# Microcontroller.net
KiCad netlist of a schematic drawn in Altium Designer
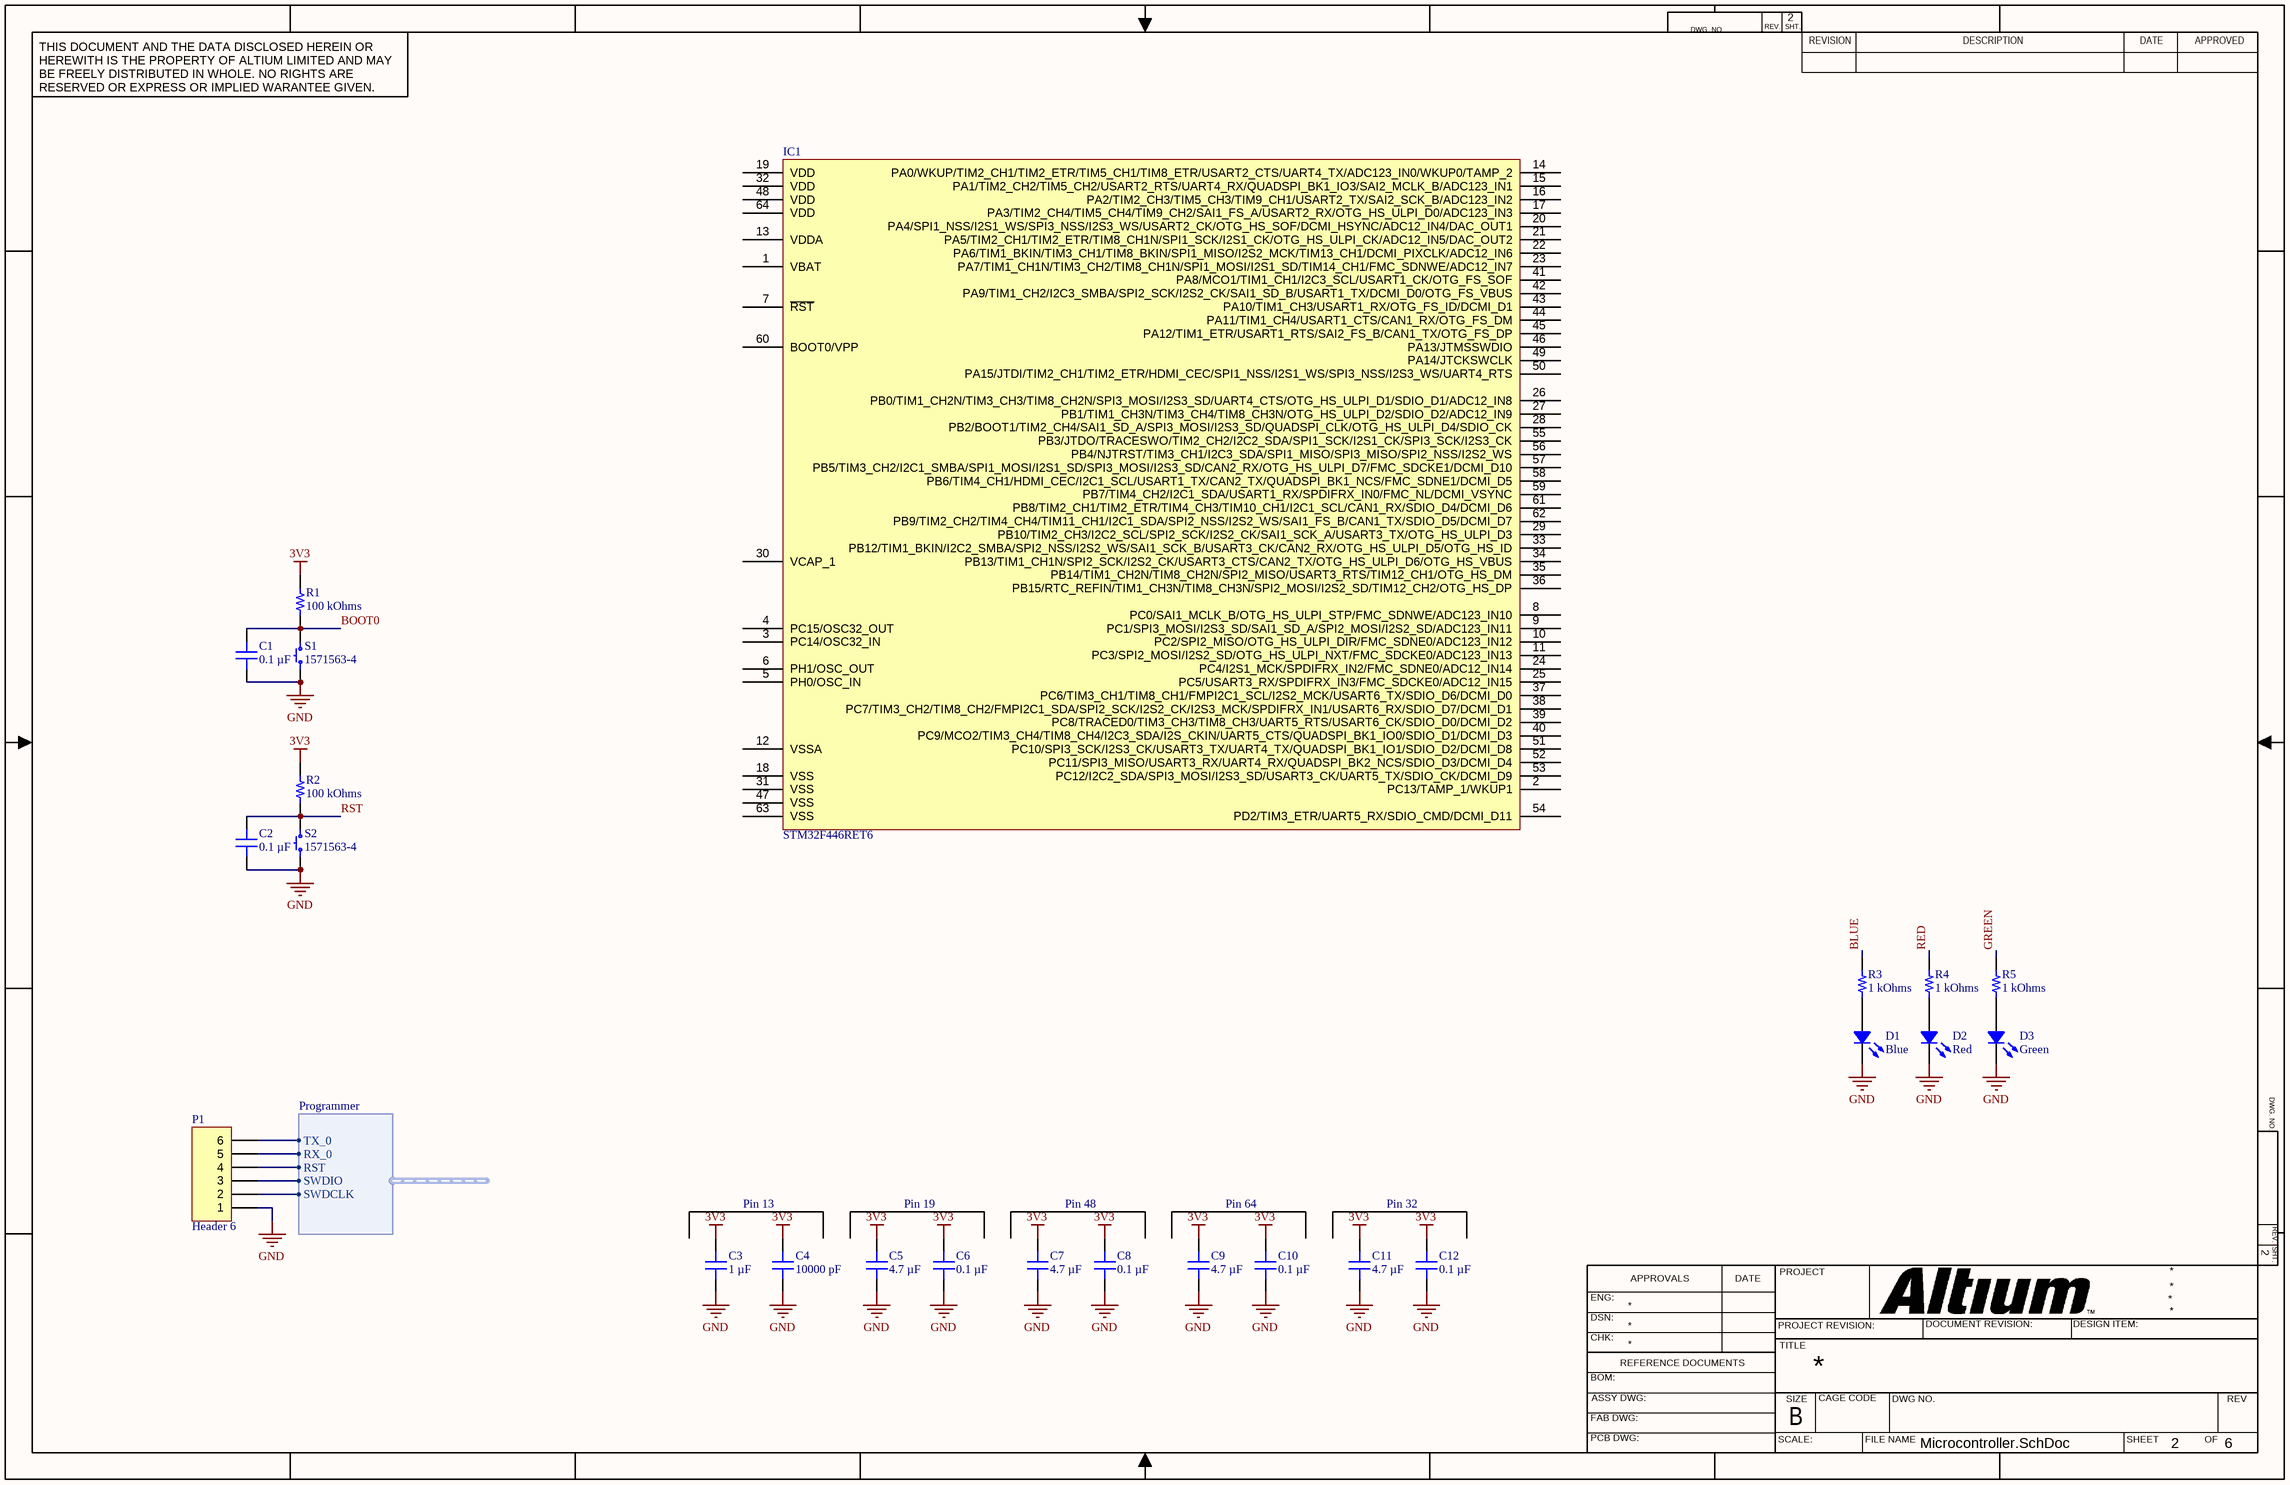
[diagram p0: Microcontroller.SchDoc]

(export (version "E")
  (design (tool "Eeschema 10.0.6"))
  (components
    (comp (ref "C1")
      (value "0.1 µF")
      (footprint "CAP 0603_1608")
      (description "CAP CER 0.1UF 50V X7R 0603")
      (fields (field (name "PART NUMBER") "C0603C104K5RAC7411") (field (name "MANUFACTURER") "KEMET"))
      (libsource (lib "Celestial Altium Library - altium_library") (part "Capacitor"))
    )
    (comp (ref "C2")
      (value "0.1 µF")
      (footprint "CAP 0603_1608")
      (description "CAP CER 0.1UF 50V X7R 0603")
      (fields (field (name "PART NUMBER") "C0603C104K5RAC7411") (field (name "MANUFACTURER") "KEMET"))
      (libsource (lib "Celestial Altium Library - altium_library") (part "Capacitor"))
    )
    (comp (ref "C3")
      (value "1 µF")
      (footprint "CAP 0603_1608")
      (description "CAP CER 1UF 10V X7R 0603")
      (fields (field (name "PART NUMBER") "CC0603KRX7R6BB105") (field (name "MANUFACTURER") "Yageo"))
      (libsource (lib "Celestial Altium Library - altium_library") (part "Capacitor"))
    )
    (comp (ref "C4")
      (value "10000 pF")
      (footprint "CAP 0603_1608")
      (description "CAP CER 0603 10NF 16V X7R 10%")
      (fields (field (name "PART NUMBER") "C0603C103K4RECAUTO") (field (name "MANUFACTURER") "KEMET"))
      (libsource (lib "Celestial Altium Library - altium_library") (part "Capacitor"))
    )
    (comp (ref "C5")
      (value "4.7 µF")
      (footprint "CAP 0603_1608")
      (description "CAP CER 4.7UF 10V X5R 0603")
      (fields
        (field (name "PART NUMBER") "CL10A475KP8NNNC")
        (field (name "MANUFACTURER") "Samsung Electro-Mechanics")
      )
      (libsource (lib "Celestial Altium Library - altium_library") (part "Capacitor"))
    )
    (comp (ref "C6")
      (value "0.1 µF")
      (footprint "CAP 0603_1608")
      (description "CAP CER 0.1UF 50V X7R 0603")
      (fields (field (name "PART NUMBER") "C0603C104K5RAC7411") (field (name "MANUFACTURER") "KEMET"))
      (libsource (lib "Celestial Altium Library - altium_library") (part "Capacitor"))
    )
    (comp (ref "C7")
      (value "4.7 µF")
      (footprint "CAP 0603_1608")
      (description "CAP CER 4.7UF 10V X5R 0603")
      (fields
        (field (name "PART NUMBER") "CL10A475KP8NNNC")
        (field (name "MANUFACTURER") "Samsung Electro-Mechanics")
      )
      (libsource (lib "Celestial Altium Library - altium_library") (part "Capacitor"))
    )
    (comp (ref "C8")
      (value "0.1 µF")
      (footprint "CAP 0603_1608")
      (description "CAP CER 0.1UF 50V X7R 0603")
      (fields (field (name "PART NUMBER") "C0603C104K5RAC7411") (field (name "MANUFACTURER") "KEMET"))
      (libsource (lib "Celestial Altium Library - altium_library") (part "Capacitor"))
    )
    (comp (ref "C9")
      (value "4.7 µF")
      (footprint "CAP 0603_1608")
      (description "CAP CER 4.7UF 10V X5R 0603")
      (fields
        (field (name "PART NUMBER") "CL10A475KP8NNNC")
        (field (name "MANUFACTURER") "Samsung Electro-Mechanics")
      )
      (libsource (lib "Celestial Altium Library - altium_library") (part "Capacitor"))
    )
    (comp (ref "C10")
      (value "0.1 µF")
      (footprint "CAP 0603_1608")
      (description "CAP CER 0.1UF 50V X7R 0603")
      (fields (field (name "PART NUMBER") "C0603C104K5RAC7411") (field (name "MANUFACTURER") "KEMET"))
      (libsource (lib "Celestial Altium Library - altium_library") (part "Capacitor"))
    )
    (comp (ref "C11")
      (value "4.7 µF")
      (footprint "CAP 0603_1608")
      (description "CAP CER 4.7UF 10V X5R 0603")
      (fields
        (field (name "PART NUMBER") "CL10A475KP8NNNC")
        (field (name "MANUFACTURER") "Samsung Electro-Mechanics")
      )
      (libsource (lib "Celestial Altium Library - altium_library") (part "Capacitor"))
    )
    (comp (ref "C12")
      (value "0.1 µF")
      (footprint "CAP 0603_1608")
      (description "CAP CER 0.1UF 50V X7R 0603")
      (fields (field (name "PART NUMBER") "C0603C104K5RAC7411") (field (name "MANUFACTURER") "KEMET"))
      (libsource (lib "Celestial Altium Library - altium_library") (part "Capacitor"))
    )
    (comp (ref "D1")
      (value "Blue")
      (footprint "LED 0603_1608 BLUE")
      (description "LED BLUE CLEAR CHIP SMD")
      (fields (field (name "PART NUMBER") "LTST-C193TBKT-5A") (field (name "MANUFACTURER") "Lite-On Inc."))
      (libsource (lib "Celestial Altium Library - altium_library") (part "LED"))
    )
    (comp (ref "D2")
      (value "Red")
      (footprint "LED 0603_1608 RED")
      (description "LED RED CLEAR CHIP SMD")
      (fields (field (name "PART NUMBER") "LTST-C190KAKT") (field (name "MANUFACTURER") "Lite-On Inc."))
      (libsource (lib "Celestial Altium Library - altium_library") (part "LED"))
    )
    (comp (ref "D3")
      (value "Green")
      (footprint "LED 0603_1608 GREEN")
      (description "LED GREEN CLEAR 2SMD")
      (fields (field (name "PART NUMBER") "XZVGT53W-6") (field (name "MANUFACTURER") "SunLED"))
      (libsource (lib "Celestial Altium Library - altium_library") (part "LED"))
    )
    (comp (ref "IC1")
      (value "STM32F446RET6")
      (footprint "ST LQFP-64 10X10MM")
      (description "IC MCU 32BIT 512KB FLASH 64LQFP")
      (fields (field (name "MANUFACTURER") "STMicroelectronics"))
      (libsource (lib "Celestial Altium Library - altium_library") (part "ST STM32F446 64PIN"))
    )
    (comp (ref "P1")
      (value "Header 6")
      (footprint "HDR1X6")
      (description "Header, 6-Pin")
      (fields (field (name "PUBLISHER") "Altium Limited"))
      (libsource (lib "Miscellaneous Connectors") (part "Header 6"))
    )
    (comp (ref "R1")
      (value "100 kOhms")
      (footprint "RES 0603_1608")
      (description "RES 100K OHM 1% 1/10W 0603")
      (fields (field (name "PART NUMBER") "CRCW0603100KFKEAC") (field (name "MANUFACTURER") "Vishay Dale"))
      (libsource (lib "Celestial Altium Library - altium_library") (part "Resistor"))
    )
    (comp (ref "R2")
      (value "100 kOhms")
      (footprint "RES 0603_1608")
      (description "RES 100K OHM 1% 1/10W 0603")
      (fields (field (name "PART NUMBER") "CRCW0603100KFKEAC") (field (name "MANUFACTURER") "Vishay Dale"))
      (libsource (lib "Celestial Altium Library - altium_library") (part "Resistor"))
    )
    (comp (ref "R3")
      (value "1 kOhms")
      (footprint "RES 0603_1608")
      (description "RES SMD 1K OHM 1% 1/10W 0603")
      (fields (field (name "PART NUMBER") "RT0603FRE071KL") (field (name "MANUFACTURER") "Yageo"))
      (libsource (lib "Celestial Altium Library - altium_library") (part "Resistor"))
    )
    (comp (ref "R4")
      (value "1 kOhms")
      (footprint "RES 0603_1608")
      (description "RES SMD 1K OHM 1% 1/10W 0603")
      (fields (field (name "PART NUMBER") "RT0603FRE071KL") (field (name "MANUFACTURER") "Yageo"))
      (libsource (lib "Celestial Altium Library - altium_library") (part "Resistor"))
    )
    (comp (ref "R5")
      (value "1 kOhms")
      (footprint "RES 0603_1608")
      (description "RES SMD 1K OHM 1% 1/10W 0603")
      (fields (field (name "PART NUMBER") "RT0603FRE071KL") (field (name "MANUFACTURER") "Yageo"))
      (libsource (lib "Celestial Altium Library - altium_library") (part "Resistor"))
    )
    (comp (ref "S1")
      (value "1571563-4")
      (footprint "TE FSM4JSMA")
      (description "SWITCH TACTILE SPST-NO 0.05A 24V")
      (fields (field (name "MANUFACTURER") "TE Connectivity ALCOSWITCH Switches"))
      (libsource (lib "Celestial Altium Library - altium_library") (part "SPST-NO 4 PIN"))
    )
    (comp (ref "S2")
      (value "1571563-4")
      (footprint "TE FSM4JSMA")
      (description "SWITCH TACTILE SPST-NO 0.05A 24V")
      (fields (field (name "MANUFACTURER") "TE Connectivity ALCOSWITCH Switches"))
      (libsource (lib "Celestial Altium Library - altium_library") (part "SPST-NO 4 PIN"))
    )
  )
  (nets
    (net (code "2") (name "/BLUE") (class "Default")
      (node (ref "R3") (pin "2") (pinfunction "2_2") (pintype "passive"))
    )
    (net (code "3") (name "/BOOT0") (class "Default")
      (node (ref "C1") (pin "2") (pinfunction "2_2") (pintype "passive"))
      (node (ref "R1") (pin "1") (pinfunction "1_1") (pintype "passive"))
      (node (ref "S1") (pin "3") (pinfunction "3_3") (pintype "passive"))
      (node (ref "S1") (pin "4") (pinfunction "4_4") (pintype "passive"))
    )
    (net (code "4") (name "/GREEN") (class "Default")
      (node (ref "R5") (pin "2") (pinfunction "2_2") (pintype "passive"))
    )
    (net (code "5") (name "/RED") (class "Default")
      (node (ref "R4") (pin "2") (pinfunction "2_2") (pintype "passive"))
    )
    (net (code "6") (name "/RST") (class "Default")
      (node (ref "C2") (pin "2") (pinfunction "2_2") (pintype "passive"))
      (node (ref "R2") (pin "1") (pinfunction "1_1") (pintype "passive"))
      (node (ref "S2") (pin "3") (pinfunction "3_3") (pintype "passive"))
      (node (ref "S2") (pin "4") (pinfunction "4_4") (pintype "passive"))
    )
    (net (code "7") (name "/RX_0") (class "Default")
      (node (ref "P1") (pin "5") (pinfunction "5_5") (pintype "passive"))
    )
    (net (code "8") (name "/SWDCLK") (class "Default")
      (node (ref "P1") (pin "2") (pinfunction "2_2") (pintype "passive"))
    )
    (net (code "9") (name "/SWDIO") (class "Default")
      (node (ref "P1") (pin "3") (pinfunction "3_3") (pintype "passive"))
    )
    (net (code "10") (name "/TX_0") (class "Default")
      (node (ref "P1") (pin "6") (pinfunction "6_6") (pintype "passive"))
    )
    (net (code "12") (name "3V3") (class "Default")
      (node (ref "C10") (pin "2") (pinfunction "2_2") (pintype "passive"))
      (node (ref "C11") (pin "2") (pinfunction "2_2") (pintype "passive"))
      (node (ref "C12") (pin "2") (pinfunction "2_2") (pintype "passive"))
      (node (ref "C3") (pin "2") (pinfunction "2_2") (pintype "passive"))
      (node (ref "C4") (pin "2") (pinfunction "2_2") (pintype "passive"))
      (node (ref "C5") (pin "2") (pinfunction "2_2") (pintype "passive"))
      (node (ref "C6") (pin "2") (pinfunction "2_2") (pintype "passive"))
      (node (ref "C7") (pin "2") (pinfunction "2_2") (pintype "passive"))
      (node (ref "C8") (pin "2") (pinfunction "2_2") (pintype "passive"))
      (node (ref "C9") (pin "2") (pinfunction "2_2") (pintype "passive"))
      (node (ref "R1") (pin "2") (pinfunction "2_2") (pintype "passive"))
      (node (ref "R2") (pin "2") (pinfunction "2_2") (pintype "passive"))
    )
    (net (code "13") (name "GND") (class "Default")
      (node (ref "C1") (pin "1") (pinfunction "1_1") (pintype "passive"))
      (node (ref "C10") (pin "1") (pinfunction "1_1") (pintype "passive"))
      (node (ref "C11") (pin "1") (pinfunction "1_1") (pintype "passive"))
      (node (ref "C12") (pin "1") (pinfunction "1_1") (pintype "passive"))
      (node (ref "C2") (pin "1") (pinfunction "1_1") (pintype "passive"))
      (node (ref "C3") (pin "1") (pinfunction "1_1") (pintype "passive"))
      (node (ref "C4") (pin "1") (pinfunction "1_1") (pintype "passive"))
      (node (ref "C5") (pin "1") (pinfunction "1_1") (pintype "passive"))
      (node (ref "C6") (pin "1") (pinfunction "1_1") (pintype "passive"))
      (node (ref "C7") (pin "1") (pinfunction "1_1") (pintype "passive"))
      (node (ref "C8") (pin "1") (pinfunction "1_1") (pintype "passive"))
      (node (ref "C9") (pin "1") (pinfunction "1_1") (pintype "passive"))
      (node (ref "D1") (pin "2") (pinfunction "2_2") (pintype "passive"))
      (node (ref "D2") (pin "2") (pinfunction "2_2") (pintype "passive"))
      (node (ref "D3") (pin "2") (pinfunction "2_2") (pintype "passive"))
      (node (ref "P1") (pin "1") (pinfunction "1_1") (pintype "passive"))
      (node (ref "S1") (pin "1") (pinfunction "1_1") (pintype "passive"))
      (node (ref "S1") (pin "2") (pinfunction "2_2") (pintype "passive"))
      (node (ref "S2") (pin "1") (pinfunction "1_1") (pintype "passive"))
      (node (ref "S2") (pin "2") (pinfunction "2_2") (pintype "passive"))
    )
    (net (code "14") (name "Net-(D1-Pad1)") (class "Default")
      (node (ref "D1") (pin "1") (pinfunction "1_1") (pintype "passive"))
      (node (ref "R3") (pin "1") (pinfunction "1_1") (pintype "passive"))
    )
    (net (code "15") (name "Net-(D2-Pad1)") (class "Default")
      (node (ref "D2") (pin "1") (pinfunction "1_1") (pintype "passive"))
      (node (ref "R4") (pin "1") (pinfunction "1_1") (pintype "passive"))
    )
    (net (code "16") (name "Net-(D3-Pad1)") (class "Default")
      (node (ref "D3") (pin "1") (pinfunction "1_1") (pintype "passive"))
      (node (ref "R5") (pin "1") (pinfunction "1_1") (pintype "passive"))
    )
    (net (code "17") (name "unconnected-(IC1-BOOT0{slash}VPP-Pad60)") (class "Default")
      (node (ref "IC1") (pin "60") (pinfunction "BOOT0/VPP_60") (pintype "passive"))
    )
    (net (code "18") (name "unconnected-(IC1-PA0{slash}WKUP{slash}TIM2_CH1{slash}TIM2_ETR{slash}TIM5_CH1{slash}TIM8_ETR{slash}USART2_CTS{slash}UART4_TX{slash}ADC123_IN0{slash}WKUP0{slash}TAMP_2-Pad14)") (class "Default")
      (node (ref "IC1") (pin "14") (pinfunction "PA0/WKUP/TIM2_CH1/TIM2_ETR/TIM5_CH1/TIM8_ETR/USART2_CTS/UART4_TX/ADC123_IN0/WKUP0/TAMP_2_14") (pintype "passive"))
    )
    (net (code "19") (name "unconnected-(IC1-PA1{slash}TIM2_CH2{slash}TIM5_CH2{slash}USART2_RTS{slash}UART4_RX{slash}QUADSPI_BK1_IO3{slash}SAI2_MCLK_B{slash}ADC123_IN1-Pad15)") (class "Default")
      (node (ref "IC1") (pin "15") (pinfunction "PA1/TIM2_CH2/TIM5_CH2/USART2_RTS/UART4_RX/QUADSPI_BK1_IO3/SAI2_MCLK_B/ADC123_IN1_15") (pintype "passive"))
    )
    (net (code "20") (name "unconnected-(IC1-PA2{slash}TIM2_CH3{slash}TIM5_CH3{slash}TIM9_CH1{slash}USART2_TX{slash}SAI2_SCK_B{slash}ADC123_IN2-Pad16)") (class "Default")
      (node (ref "IC1") (pin "16") (pinfunction "PA2/TIM2_CH3/TIM5_CH3/TIM9_CH1/USART2_TX/SAI2_SCK_B/ADC123_IN2_16") (pintype "passive"))
    )
    (net (code "21") (name "unconnected-(IC1-PA3{slash}TIM2_CH4{slash}TIM5_CH4{slash}TIM9_CH2{slash}SAI1_FS_A{slash}USART2_RX{slash}OTG_HS_ULPI_D0{slash}ADC123_IN3-Pad17)") (class "Default")
      (node (ref "IC1") (pin "17") (pinfunction "PA3/TIM2_CH4/TIM5_CH4/TIM9_CH2/SAI1_FS_A/USART2_RX/OTG_HS_ULPI_D0/ADC123_IN3_17") (pintype "passive"))
    )
    (net (code "22") (name "unconnected-(IC1-PA4{slash}SPI1_NSS{slash}I2S1_WS{slash}SPI3_NSS{slash}I2S3_WS{slash}USART2_CK{slash}OTG_HS_SOF{slash}DCMI_HSYNC{slash}ADC12_IN4{slash}DAC_OUT1-Pad20)") (class "Default")
      (node (ref "IC1") (pin "20") (pinfunction "PA4/SPI1_NSS/I2S1_WS/SPI3_NSS/I2S3_WS/USART2_CK/OTG_HS_SOF/DCMI_HSYNC/ADC12_IN4/DAC_OUT1_20") (pintype "passive"))
    )
    (net (code "23") (name "unconnected-(IC1-PA5{slash}TIM2_CH1{slash}TIM2_ETR{slash}TIM8_CH1N{slash}SPI1_SCK{slash}I2S1_CK{slash}OTG_HS_ULPI_CK{slash}ADC12_IN5{slash}DAC_OUT2-Pad21)") (class "Default")
      (node (ref "IC1") (pin "21") (pinfunction "PA5/TIM2_CH1/TIM2_ETR/TIM8_CH1N/SPI1_SCK/I2S1_CK/OTG_HS_ULPI_CK/ADC12_IN5/DAC_OUT2_21") (pintype "passive"))
    )
    (net (code "24") (name "unconnected-(IC1-PA6{slash}TIM1_BKIN{slash}TIM3_CH1{slash}TIM8_BKIN{slash}SPI1_MISO{slash}I2S2_MCK{slash}TIM13_CH1{slash}DCMI_PIXCLK{slash}ADC12_IN6-Pad22)") (class "Default")
      (node (ref "IC1") (pin "22") (pinfunction "PA6/TIM1_BKIN/TIM3_CH1/TIM8_BKIN/SPI1_MISO/I2S2_MCK/TIM13_CH1/DCMI_PIXCLK/ADC12_IN6_22") (pintype "passive"))
    )
    (net (code "25") (name "unconnected-(IC1-PA7{slash}TIM1_CH1N{slash}TIM3_CH2{slash}TIM8_CH1N{slash}SPI1_MOSI{slash}I2S1_SD{slash}TIM14_CH1{slash}FMC_SDNWE{slash}ADC12_IN7-Pad23)") (class "Default")
      (node (ref "IC1") (pin "23") (pinfunction "PA7/TIM1_CH1N/TIM3_CH2/TIM8_CH1N/SPI1_MOSI/I2S1_SD/TIM14_CH1/FMC_SDNWE/ADC12_IN7_23") (pintype "passive"))
    )
    (net (code "26") (name "unconnected-(IC1-PA8{slash}MCO1{slash}TIM1_CH1{slash}I2C3_SCL{slash}USART1_CK{slash}OTG_FS_SOF-Pad41)") (class "Default")
      (node (ref "IC1") (pin "41") (pinfunction "PA8/MCO1/TIM1_CH1/I2C3_SCL/USART1_CK/OTG_FS_SOF_41") (pintype "passive"))
    )
    (net (code "27") (name "unconnected-(IC1-PA9{slash}TIM1_CH2{slash}I2C3_SMBA{slash}SPI2_SCK{slash}I2S2_CK{slash}SAI1_SD_B{slash}USART1_TX{slash}DCMI_D0{slash}OTG_FS_VBUS-Pad42)") (class "Default")
      (node (ref "IC1") (pin "42") (pinfunction "PA9/TIM1_CH2/I2C3_SMBA/SPI2_SCK/I2S2_CK/SAI1_SD_B/USART1_TX/DCMI_D0/OTG_FS_VBUS_42") (pintype "passive"))
    )
    (net (code "28") (name "unconnected-(IC1-PA10{slash}TIM1_CH3{slash}USART1_RX{slash}OTG_FS_ID{slash}DCMI_D1-Pad43)") (class "Default")
      (node (ref "IC1") (pin "43") (pinfunction "PA10/TIM1_CH3/USART1_RX/OTG_FS_ID/DCMI_D1_43") (pintype "passive"))
    )
    (net (code "29") (name "unconnected-(IC1-PA11{slash}TIM1_CH4{slash}USART1_CTS{slash}CAN1_RX{slash}OTG_FS_DM-Pad44)") (class "Default")
      (node (ref "IC1") (pin "44") (pinfunction "PA11/TIM1_CH4/USART1_CTS/CAN1_RX/OTG_FS_DM_44") (pintype "passive"))
    )
    (net (code "30") (name "unconnected-(IC1-PA12{slash}TIM1_ETR{slash}USART1_RTS{slash}SAI2_FS_B{slash}CAN1_TX{slash}OTG_FS_DP-Pad45)") (class "Default")
      (node (ref "IC1") (pin "45") (pinfunction "PA12/TIM1_ETR/USART1_RTS/SAI2_FS_B/CAN1_TX/OTG_FS_DP_45") (pintype "passive"))
    )
    (net (code "31") (name "unconnected-(IC1-PA13{slash}JTMSSWDIO-Pad46)") (class "Default")
      (node (ref "IC1") (pin "46") (pinfunction "PA13/JTMSSWDIO_46") (pintype "passive"))
    )
    (net (code "32") (name "unconnected-(IC1-PA14{slash}JTCKSWCLK-Pad49)") (class "Default")
      (node (ref "IC1") (pin "49") (pinfunction "PA14/JTCKSWCLK_49") (pintype "passive"))
    )
    (net (code "33") (name "unconnected-(IC1-PA15{slash}JTDI{slash}TIM2_CH1{slash}TIM2_ETR{slash}HDMI_CEC{slash}SPI1_NSS{slash}I2S1_WS{slash}SPI3_NSS{slash}I2S3_WS{slash}UART4_RTS-Pad50)") (class "Default")
      (node (ref "IC1") (pin "50") (pinfunction "PA15/JTDI/TIM2_CH1/TIM2_ETR/HDMI_CEC/SPI1_NSS/I2S1_WS/SPI3_NSS/I2S3_WS/UART4_RTS_50") (pintype "passive"))
    )
    (net (code "34") (name "unconnected-(IC1-PB0{slash}TIM1_CH2N{slash}TIM3_CH3{slash}TIM8_CH2N{slash}SPI3_MOSI{slash}I2S3_SD{slash}UART4_CTS{slash}OTG_HS_ULPI_D1{slash}SDIO_D1{slash}ADC12_IN8-Pad26)") (class "Default")
      (node (ref "IC1") (pin "26") (pinfunction "PB0/TIM1_CH2N/TIM3_CH3/TIM8_CH2N/SPI3_MOSI/I2S3_SD/UART4_CTS/OTG_HS_ULPI_D1/SDIO_D1/ADC12_IN8_26") (pintype "passive"))
    )
    (net (code "35") (name "unconnected-(IC1-PB1{slash}TIM1_CH3N{slash}TIM3_CH4{slash}TIM8_CH3N{slash}OTG_HS_ULPI_D2{slash}SDIO_D2{slash}ADC12_IN9-Pad27)") (class "Default")
      (node (ref "IC1") (pin "27") (pinfunction "PB1/TIM1_CH3N/TIM3_CH4/TIM8_CH3N/OTG_HS_ULPI_D2/SDIO_D2/ADC12_IN9_27") (pintype "passive"))
    )
    (net (code "36") (name "unconnected-(IC1-PB2{slash}BOOT1{slash}TIM2_CH4{slash}SAI1_SD_A{slash}SPI3_MOSI{slash}I2S3_SD{slash}QUADSPI_CLK{slash}OTG_HS_ULPI_D4{slash}SDIO_CK-Pad28)") (class "Default")
      (node (ref "IC1") (pin "28") (pinfunction "PB2/BOOT1/TIM2_CH4/SAI1_SD_A/SPI3_MOSI/I2S3_SD/QUADSPI_CLK/OTG_HS_ULPI_D4/SDIO_CK_28") (pintype "passive"))
    )
    (net (code "37") (name "unconnected-(IC1-PB3{slash}JTDO{slash}TRACESWO{slash}TIM2_CH2{slash}I2C2_SDA{slash}SPI1_SCK{slash}I2S1_CK{slash}SPI3_SCK{slash}I2S3_CK-Pad55)") (class "Default")
      (node (ref "IC1") (pin "55") (pinfunction "PB3/JTDO/TRACESWO/TIM2_CH2/I2C2_SDA/SPI1_SCK/I2S1_CK/SPI3_SCK/I2S3_CK_55") (pintype "passive"))
    )
    (net (code "38") (name "unconnected-(IC1-PB4{slash}NJTRST{slash}TIM3_CH1{slash}I2C3_SDA{slash}SPI1_MISO{slash}SPI3_MISO{slash}SPI2_NSS{slash}I2S2_WS-Pad56)") (class "Default")
      (node (ref "IC1") (pin "56") (pinfunction "PB4/NJTRST/TIM3_CH1/I2C3_SDA/SPI1_MISO/SPI3_MISO/SPI2_NSS/I2S2_WS_56") (pintype "passive"))
    )
    (net (code "39") (name "unconnected-(IC1-PB5{slash}TIM3_CH2{slash}I2C1_SMBA{slash}SPI1_MOSI{slash}I2S1_SD{slash}SPI3_MOSI{slash}I2S3_SD{slash}CAN2_RX{slash}OTG_HS_ULPI_D7{slash}FMC_SDCKE1{slash}DCMI_D10-Pad57)") (class "Default")
      (node (ref "IC1") (pin "57") (pinfunction "PB5/TIM3_CH2/I2C1_SMBA/SPI1_MOSI/I2S1_SD/SPI3_MOSI/I2S3_SD/CAN2_RX/OTG_HS_ULPI_D7/FMC_SDCKE1/DCMI_D10_57") (pintype "passive"))
    )
    (net (code "40") (name "unconnected-(IC1-PB6{slash}TIM4_CH1{slash}HDMI_CEC{slash}I2C1_SCL{slash}USART1_TX{slash}CAN2_TX{slash}QUADSPI_BK1_NCS{slash}FMC_SDNE1{slash}DCMI_D5-Pad58)") (class "Default")
      (node (ref "IC1") (pin "58") (pinfunction "PB6/TIM4_CH1/HDMI_CEC/I2C1_SCL/USART1_TX/CAN2_TX/QUADSPI_BK1_NCS/FMC_SDNE1/DCMI_D5_58") (pintype "passive"))
    )
    (net (code "41") (name "unconnected-(IC1-PB7{slash}TIM4_CH2{slash}I2C1_SDA{slash}USART1_RX{slash}SPDIFRX_IN0{slash}FMC_NL{slash}DCMI_VSYNC-Pad59)") (class "Default")
      (node (ref "IC1") (pin "59") (pinfunction "PB7/TIM4_CH2/I2C1_SDA/USART1_RX/SPDIFRX_IN0/FMC_NL/DCMI_VSYNC_59") (pintype "passive"))
    )
    (net (code "42") (name "unconnected-(IC1-PB8{slash}TIM2_CH1{slash}TIM2_ETR{slash}TIM4_CH3{slash}TIM10_CH1{slash}I2C1_SCL{slash}CAN1_RX{slash}SDIO_D4{slash}DCMI_D6-Pad61)") (class "Default")
      (node (ref "IC1") (pin "61") (pinfunction "PB8/TIM2_CH1/TIM2_ETR/TIM4_CH3/TIM10_CH1/I2C1_SCL/CAN1_RX/SDIO_D4/DCMI_D6_61") (pintype "passive"))
    )
    (net (code "43") (name "unconnected-(IC1-PB9{slash}TIM2_CH2{slash}TIM4_CH4{slash}TIM11_CH1{slash}I2C1_SDA{slash}SPI2_NSS{slash}I2S2_WS{slash}SAI1_FS_B{slash}CAN1_TX{slash}SDIO_D5{slash}DCMI_D7-Pad62)") (class "Default")
      (node (ref "IC1") (pin "62") (pinfunction "PB9/TIM2_CH2/TIM4_CH4/TIM11_CH1/I2C1_SDA/SPI2_NSS/I2S2_WS/SAI1_FS_B/CAN1_TX/SDIO_D5/DCMI_D7_62") (pintype "passive"))
    )
    (net (code "44") (name "unconnected-(IC1-PB10{slash}TIM2_CH3{slash}I2C2_SCL{slash}SPI2_SCK{slash}I2S2_CK{slash}SAI1_SCK_A{slash}USART3_TX{slash}OTG_HS_ULPI_D3-Pad29)") (class "Default")
      (node (ref "IC1") (pin "29") (pinfunction "PB10/TIM2_CH3/I2C2_SCL/SPI2_SCK/I2S2_CK/SAI1_SCK_A/USART3_TX/OTG_HS_ULPI_D3_29") (pintype "passive"))
    )
    (net (code "45") (name "unconnected-(IC1-PB12{slash}TIM1_BKIN{slash}I2C2_SMBA{slash}SPI2_NSS{slash}I2S2_WS{slash}SAI1_SCK_B{slash}USART3_CK{slash}CAN2_RX{slash}OTG_HS_ULPI_D5{slash}OTG_HS_ID-Pad33)") (class "Default")
      (node (ref "IC1") (pin "33") (pinfunction "PB12/TIM1_BKIN/I2C2_SMBA/SPI2_NSS/I2S2_WS/SAI1_SCK_B/USART3_CK/CAN2_RX/OTG_HS_ULPI_D5/OTG_HS_ID_33") (pintype "passive"))
    )
    (net (code "46") (name "unconnected-(IC1-PB13{slash}TIM1_CH1N{slash}SPI2_SCK{slash}I2S2_CK{slash}USART3_CTS{slash}CAN2_TX{slash}OTG_HS_ULPI_D6{slash}OTG_HS_VBUS-Pad34)") (class "Default")
      (node (ref "IC1") (pin "34") (pinfunction "PB13/TIM1_CH1N/SPI2_SCK/I2S2_CK/USART3_CTS/CAN2_TX/OTG_HS_ULPI_D6/OTG_HS_VBUS_34") (pintype "passive"))
    )
    (net (code "47") (name "unconnected-(IC1-PB14{slash}TIM1_CH2N{slash}TIM8_CH2N{slash}SPI2_MISO{slash}USART3_RTS{slash}TIM12_CH1{slash}OTG_HS_DM-Pad35)") (class "Default")
      (node (ref "IC1") (pin "35") (pinfunction "PB14/TIM1_CH2N/TIM8_CH2N/SPI2_MISO/USART3_RTS/TIM12_CH1/OTG_HS_DM_35") (pintype "passive"))
    )
    (net (code "48") (name "unconnected-(IC1-PB15{slash}RTC_REFIN{slash}TIM1_CH3N{slash}TIM8_CH3N{slash}SPI2_MOSI{slash}I2S2_SD{slash}TIM12_CH2{slash}OTG_HS_DP-Pad36)") (class "Default")
      (node (ref "IC1") (pin "36") (pinfunction "PB15/RTC_REFIN/TIM1_CH3N/TIM8_CH3N/SPI2_MOSI/I2S2_SD/TIM12_CH2/OTG_HS_DP_36") (pintype "passive"))
    )
    (net (code "49") (name "unconnected-(IC1-PC0{slash}SAI1_MCLK_B{slash}OTG_HS_ULPI_STP{slash}FMC_SDNWE{slash}ADC123_IN10-Pad8)") (class "Default")
      (node (ref "IC1") (pin "8") (pinfunction "PC0/SAI1_MCLK_B/OTG_HS_ULPI_STP/FMC_SDNWE/ADC123_IN10_8") (pintype "passive"))
    )
    (net (code "50") (name "unconnected-(IC1-PC1{slash}SPI3_MOSI{slash}I2S3_SD{slash}SAI1_SD_A{slash}SPI2_MOSI{slash}I2S2_SD{slash}ADC123_IN11-Pad9)") (class "Default")
      (node (ref "IC1") (pin "9") (pinfunction "PC1/SPI3_MOSI/I2S3_SD/SAI1_SD_A/SPI2_MOSI/I2S2_SD/ADC123_IN11_9") (pintype "passive"))
    )
    (net (code "51") (name "unconnected-(IC1-PC2{slash}SPI2_MISO{slash}OTG_HS_ULPI_DIR{slash}FMC_SDNE0{slash}ADC123_IN12-Pad10)") (class "Default")
      (node (ref "IC1") (pin "10") (pinfunction "PC2/SPI2_MISO/OTG_HS_ULPI_DIR/FMC_SDNE0/ADC123_IN12_10") (pintype "passive"))
    )
    (net (code "52") (name "unconnected-(IC1-PC3{slash}SPI2_MOSI{slash}I2S2_SD{slash}OTG_HS_ULPI_NXT{slash}FMC_SDCKE0{slash}ADC123_IN13-Pad11)") (class "Default")
      (node (ref "IC1") (pin "11") (pinfunction "PC3/SPI2_MOSI/I2S2_SD/OTG_HS_ULPI_NXT/FMC_SDCKE0/ADC123_IN13_11") (pintype "passive"))
    )
    (net (code "53") (name "unconnected-(IC1-PC4{slash}I2S1_MCK{slash}SPDIFRX_IN2{slash}FMC_SDNE0{slash}ADC12_IN14-Pad24)") (class "Default")
      (node (ref "IC1") (pin "24") (pinfunction "PC4/I2S1_MCK/SPDIFRX_IN2/FMC_SDNE0/ADC12_IN14_24") (pintype "passive"))
    )
    (net (code "54") (name "unconnected-(IC1-PC5{slash}USART3_RX{slash}SPDIFRX_IN3{slash}FMC_SDCKE0{slash}ADC12_IN15-Pad25)") (class "Default")
      (node (ref "IC1") (pin "25") (pinfunction "PC5/USART3_RX/SPDIFRX_IN3/FMC_SDCKE0/ADC12_IN15_25") (pintype "passive"))
    )
    (net (code "55") (name "unconnected-(IC1-PC6{slash}TIM3_CH1{slash}TIM8_CH1{slash}FMPI2C1_SCL{slash}I2S2_MCK{slash}USART6_TX{slash}SDIO_D6{slash}DCMI_D0-Pad37)") (class "Default")
      (node (ref "IC1") (pin "37") (pinfunction "PC6/TIM3_CH1/TIM8_CH1/FMPI2C1_SCL/I2S2_MCK/USART6_TX/SDIO_D6/DCMI_D0_37") (pintype "passive"))
    )
    (net (code "56") (name "unconnected-(IC1-PC7{slash}TIM3_CH2{slash}TIM8_CH2{slash}FMPI2C1_SDA{slash}SPI2_SCK{slash}I2S2_CK{slash}I2S3_MCK{slash}SPDIFRX_IN1{slash}USART6_RX{slash}SDIO_D7{slash}DCMI_D1-Pad38)") (class "Default")
      (node (ref "IC1") (pin "38") (pinfunction "PC7/TIM3_CH2/TIM8_CH2/FMPI2C1_SDA/SPI2_SCK/I2S2_CK/I2S3_MCK/SPDIFRX_IN1/USART6_RX/SDIO_D7/DCMI_D1_38") (pintype "passive"))
    )
    (net (code "57") (name "unconnected-(IC1-PC8{slash}TRACED0{slash}TIM3_CH3{slash}TIM8_CH3{slash}UART5_RTS{slash}USART6_CK{slash}SDIO_D0{slash}DCMI_D2-Pad39)") (class "Default")
      (node (ref "IC1") (pin "39") (pinfunction "PC8/TRACED0/TIM3_CH3/TIM8_CH3/UART5_RTS/USART6_CK/SDIO_D0/DCMI_D2_39") (pintype "passive"))
    )
    (net (code "58") (name "unconnected-(IC1-PC9{slash}MCO2{slash}TIM3_CH4{slash}TIM8_CH4{slash}I2C3_SDA{slash}I2S_CKIN{slash}UART5_CTS{slash}QUADSPI_BK1_IO0{slash}SDIO_D1{slash}DCMI_D3-Pad40)") (class "Default")
      (node (ref "IC1") (pin "40") (pinfunction "PC9/MCO2/TIM3_CH4/TIM8_CH4/I2C3_SDA/I2S_CKIN/UART5_CTS/QUADSPI_BK1_IO0/SDIO_D1/DCMI_D3_40") (pintype "passive"))
    )
    (net (code "59") (name "unconnected-(IC1-PC10{slash}SPI3_SCK{slash}I2S3_CK{slash}USART3_TX{slash}UART4_TX{slash}QUADSPI_BK1_IO1{slash}SDIO_D2{slash}DCMI_D8-Pad51)") (class "Default")
      (node (ref "IC1") (pin "51") (pinfunction "PC10/SPI3_SCK/I2S3_CK/USART3_TX/UART4_TX/QUADSPI_BK1_IO1/SDIO_D2/DCMI_D8_51") (pintype "passive"))
    )
    (net (code "60") (name "unconnected-(IC1-PC11{slash}SPI3_MISO{slash}USART3_RX{slash}UART4_RX{slash}QUADSPI_BK2_NCS{slash}SDIO_D3{slash}DCMI_D4-Pad52)") (class "Default")
      (node (ref "IC1") (pin "52") (pinfunction "PC11/SPI3_MISO/USART3_RX/UART4_RX/QUADSPI_BK2_NCS/SDIO_D3/DCMI_D4_52") (pintype "passive"))
    )
    (net (code "61") (name "unconnected-(IC1-PC12{slash}I2C2_SDA{slash}SPI3_MOSI{slash}I2S3_SD{slash}USART3_CK{slash}UART5_TX{slash}SDIO_CK{slash}DCMI_D9-Pad53)") (class "Default")
      (node (ref "IC1") (pin "53") (pinfunction "PC12/I2C2_SDA/SPI3_MOSI/I2S3_SD/USART3_CK/UART5_TX/SDIO_CK/DCMI_D9_53") (pintype "passive"))
    )
    (net (code "62") (name "unconnected-(IC1-PC13{slash}TAMP_1{slash}WKUP1-Pad2)") (class "Default")
      (node (ref "IC1") (pin "2") (pinfunction "PC13/TAMP_1/WKUP1_2") (pintype "passive"))
    )
    (net (code "63") (name "unconnected-(IC1-PC14{slash}OSC32_IN-Pad3)") (class "Default")
      (node (ref "IC1") (pin "3") (pinfunction "PC14/OSC32_IN_3") (pintype "passive"))
    )
    (net (code "64") (name "unconnected-(IC1-PC15{slash}OSC32_OUT-Pad4)") (class "Default")
      (node (ref "IC1") (pin "4") (pinfunction "PC15/OSC32_OUT_4") (pintype "passive"))
    )
    (net (code "65") (name "unconnected-(IC1-PD2{slash}TIM3_ETR{slash}UART5_RX{slash}SDIO_CMD{slash}DCMI_D11-Pad54)") (class "Default")
      (node (ref "IC1") (pin "54") (pinfunction "PD2/TIM3_ETR/UART5_RX/SDIO_CMD/DCMI_D11_54") (pintype "passive"))
    )
    (net (code "66") (name "unconnected-(IC1-PH0{slash}OSC_IN-Pad5)") (class "Default")
      (node (ref "IC1") (pin "5") (pinfunction "PH0/OSC_IN_5") (pintype "passive"))
    )
    (net (code "67") (name "unconnected-(IC1-PH1{slash}OSC_OUT-Pad6)") (class "Default")
      (node (ref "IC1") (pin "6") (pinfunction "PH1/OSC_OUT_6") (pintype "passive"))
    )
    (net (code "68") (name "unconnected-(IC1-VBAT-Pad1)") (class "Default")
      (node (ref "IC1") (pin "1") (pinfunction "VBAT_1") (pintype "passive"))
    )
    (net (code "69") (name "unconnected-(IC1-VCAP_1-Pad30)") (class "Default")
      (node (ref "IC1") (pin "30") (pinfunction "VCAP_1_30") (pintype "passive"))
    )
    (net (code "70") (name "unconnected-(IC1-VDD-Pad19)") (class "Default")
      (node (ref "IC1") (pin "19") (pinfunction "VDD_19") (pintype "passive"))
    )
    (net (code "71") (name "unconnected-(IC1-VDD-Pad32)") (class "Default")
      (node (ref "IC1") (pin "32") (pinfunction "VDD_32") (pintype "passive"))
    )
    (net (code "72") (name "unconnected-(IC1-VDD-Pad48)") (class "Default")
      (node (ref "IC1") (pin "48") (pinfunction "VDD_48") (pintype "passive"))
    )
    (net (code "73") (name "unconnected-(IC1-VDD-Pad64)") (class "Default")
      (node (ref "IC1") (pin "64") (pinfunction "VDD_64") (pintype "passive"))
    )
    (net (code "74") (name "unconnected-(IC1-VDDA-Pad13)") (class "Default")
      (node (ref "IC1") (pin "13") (pinfunction "VDDA_13") (pintype "passive"))
    )
    (net (code "75") (name "unconnected-(IC1-VSS-Pad18)") (class "Default")
      (node (ref "IC1") (pin "18") (pinfunction "VSS_18") (pintype "passive"))
    )
    (net (code "76") (name "unconnected-(IC1-VSS-Pad31)") (class "Default")
      (node (ref "IC1") (pin "31") (pinfunction "VSS_31") (pintype "passive"))
    )
    (net (code "77") (name "unconnected-(IC1-VSS-Pad47)") (class "Default")
      (node (ref "IC1") (pin "47") (pinfunction "VSS_47") (pintype "passive"))
    )
    (net (code "78") (name "unconnected-(IC1-VSS-Pad63)") (class "Default")
      (node (ref "IC1") (pin "63") (pinfunction "VSS_63") (pintype "passive"))
    )
    (net (code "79") (name "unconnected-(IC1-VSSA-Pad12)") (class "Default")
      (node (ref "IC1") (pin "12") (pinfunction "VSSA_12") (pintype "passive"))
    )
    (net (code "80") (name "unconnected-(IC1-~{RST}-Pad7)") (class "Default")
      (node (ref "IC1") (pin "7") (pinfunction "~{RST}_7") (pintype "passive"))
    )
    (net (code "81") (name "unconnected-(P1-Pad4)") (class "Default")
      (node (ref "P1") (pin "4") (pinfunction "4_4") (pintype "passive"))
    )
  )
)
